# FAN-zero20-SHIM.net
KiCad netlist of a schematic drawn in EAGLE
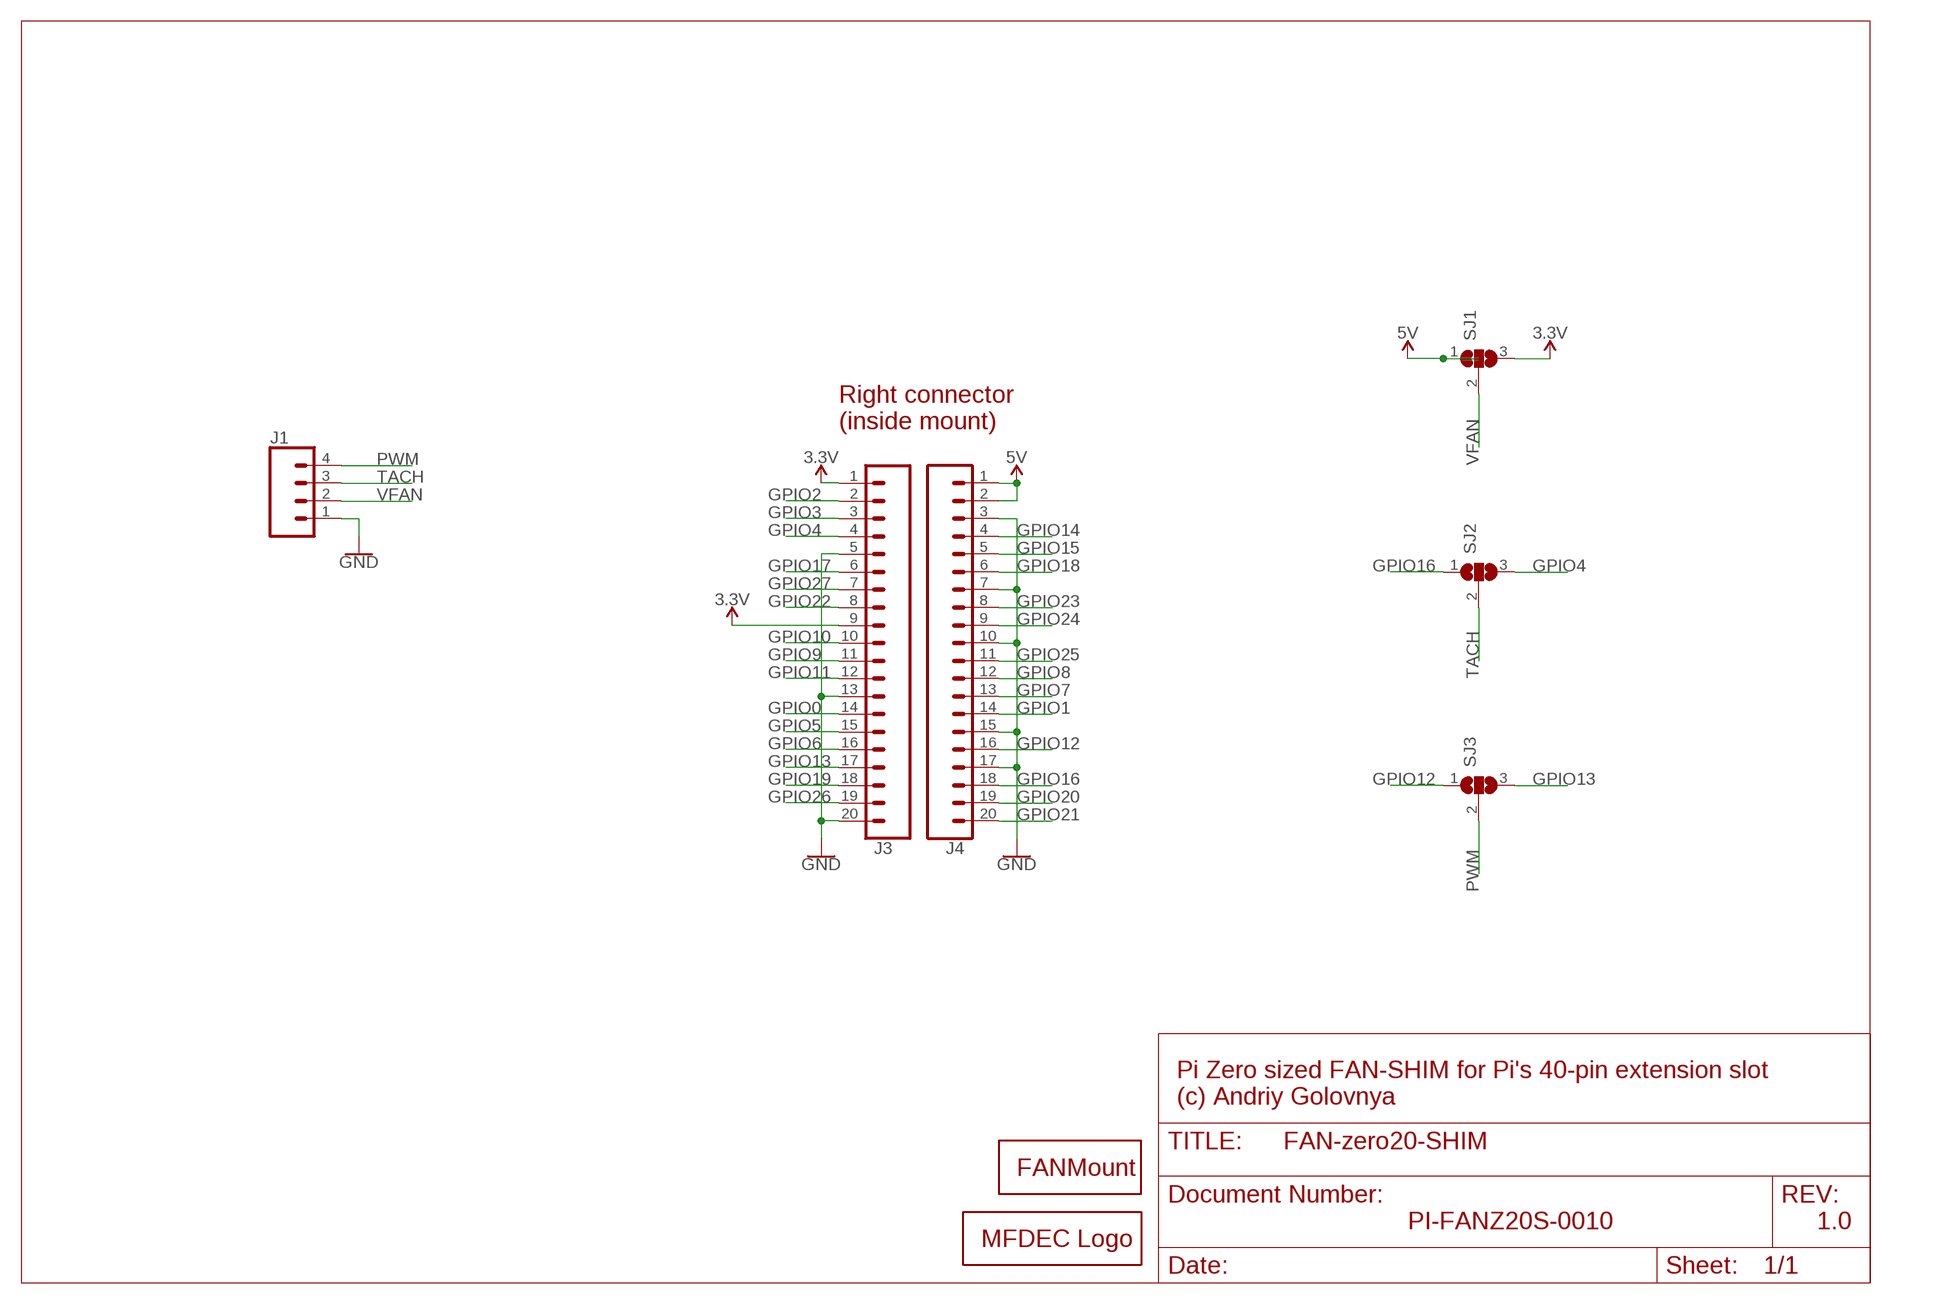
[diagram p0: schematic, sheet 1]

(export (version "E")
  (design (tool "Eeschema 10.0.6"))
  (components
    (comp (ref "FAN1")
      (value "FAN20HO")
      (footprint "eagle-import:FAN20HO")
      (libsource (lib "eagle-import") (part "FAN20HO"))
    )
    (comp (ref "J1")
      (value "CONN_04")
      (footprint "eagle-import:1X04")
      (libsource (lib "eagle-import") (part "CONN_04"))
    )
    (comp (ref "J3")
      (value "CONN_20LOCK")
      (footprint "eagle-import:1X20_LOCK")
      (libsource (lib "eagle-import") (part "CONN_20LOCK"))
    )
    (comp (ref "J4")
      (value "CONN_20LOCK")
      (footprint "eagle-import:1X20_LOCK")
      (libsource (lib "eagle-import") (part "CONN_20LOCK"))
    )
    (comp (ref "LOGO1")
      (value "MFDECLOGO_L_30MM")
      (footprint "eagle-import:MFDEC_L_30MM")
      (libsource (lib "eagle-import") (part "MFDECLOGO_L_30MM"))
    )
    (comp (ref "SJ1")
      (value "SJ2")
      (footprint "eagle-import:SJ_2")
      (libsource (lib "eagle-import") (part "SJ2"))
    )
    (comp (ref "SJ2")
      (value "SJ2")
      (footprint "eagle-import:SJ_2")
      (libsource (lib "eagle-import") (part "SJ2"))
    )
    (comp (ref "SJ3")
      (value "SJ2")
      (footprint "eagle-import:SJ_2")
      (libsource (lib "eagle-import") (part "SJ2"))
    )
  )
  (nets
    (net (code "1") (name "/GPIO0") (class "Default")
      (node (ref "J3") (pin "14") (pinfunction "14_14") (pintype "passive"))
    )
    (net (code "2") (name "/GPIO1") (class "Default")
      (node (ref "J4") (pin "14") (pinfunction "14_14") (pintype "passive"))
    )
    (net (code "3") (name "/GPIO2") (class "Default")
      (node (ref "J3") (pin "2") (pinfunction "2_2") (pintype "passive"))
    )
    (net (code "4") (name "/GPIO3") (class "Default")
      (node (ref "J3") (pin "3") (pinfunction "3_3") (pintype "passive"))
    )
    (net (code "5") (name "/GPIO4") (class "Default")
      (node (ref "J3") (pin "4") (pinfunction "4_4") (pintype "passive"))
      (node (ref "SJ2") (pin "3") (pinfunction "3_3") (pintype "passive"))
    )
    (net (code "6") (name "/GPIO5") (class "Default")
      (node (ref "J3") (pin "15") (pinfunction "15_15") (pintype "passive"))
    )
    (net (code "7") (name "/GPIO6") (class "Default")
      (node (ref "J3") (pin "16") (pinfunction "16_16") (pintype "passive"))
    )
    (net (code "8") (name "/GPIO7") (class "Default")
      (node (ref "J4") (pin "13") (pinfunction "13_13") (pintype "passive"))
    )
    (net (code "9") (name "/GPIO8") (class "Default")
      (node (ref "J4") (pin "12") (pinfunction "12_12") (pintype "passive"))
    )
    (net (code "10") (name "/GPIO9") (class "Default")
      (node (ref "J3") (pin "11") (pinfunction "11_11") (pintype "passive"))
    )
    (net (code "11") (name "/GPIO10") (class "Default")
      (node (ref "J3") (pin "10") (pinfunction "10_10") (pintype "passive"))
    )
    (net (code "12") (name "/GPIO11") (class "Default")
      (node (ref "J3") (pin "12") (pinfunction "12_12") (pintype "passive"))
    )
    (net (code "13") (name "/GPIO12") (class "Default")
      (node (ref "J4") (pin "16") (pinfunction "16_16") (pintype "passive"))
      (node (ref "SJ3") (pin "1") (pinfunction "1_1") (pintype "passive"))
    )
    (net (code "14") (name "/GPIO13") (class "Default")
      (node (ref "J3") (pin "17") (pinfunction "17_17") (pintype "passive"))
      (node (ref "SJ3") (pin "3") (pinfunction "3_3") (pintype "passive"))
    )
    (net (code "15") (name "/GPIO14") (class "Default")
      (node (ref "J4") (pin "4") (pinfunction "4_4") (pintype "passive"))
    )
    (net (code "16") (name "/GPIO15") (class "Default")
      (node (ref "J4") (pin "5") (pinfunction "5_5") (pintype "passive"))
    )
    (net (code "17") (name "/GPIO16") (class "Default")
      (node (ref "J4") (pin "18") (pinfunction "18_18") (pintype "passive"))
      (node (ref "SJ2") (pin "1") (pinfunction "1_1") (pintype "passive"))
    )
    (net (code "18") (name "/GPIO17") (class "Default")
      (node (ref "J3") (pin "6") (pinfunction "6_6") (pintype "passive"))
    )
    (net (code "19") (name "/GPIO18") (class "Default")
      (node (ref "J4") (pin "6") (pinfunction "6_6") (pintype "passive"))
    )
    (net (code "20") (name "/GPIO19") (class "Default")
      (node (ref "J3") (pin "18") (pinfunction "18_18") (pintype "passive"))
    )
    (net (code "21") (name "/GPIO20") (class "Default")
      (node (ref "J4") (pin "19") (pinfunction "19_19") (pintype "passive"))
    )
    (net (code "22") (name "/GPIO21") (class "Default")
      (node (ref "J4") (pin "20") (pinfunction "20_20") (pintype "passive"))
    )
    (net (code "23") (name "/GPIO22") (class "Default")
      (node (ref "J3") (pin "8") (pinfunction "8_8") (pintype "passive"))
    )
    (net (code "24") (name "/GPIO23") (class "Default")
      (node (ref "J4") (pin "8") (pinfunction "8_8") (pintype "passive"))
    )
    (net (code "25") (name "/GPIO24") (class "Default")
      (node (ref "J4") (pin "9") (pinfunction "9_9") (pintype "passive"))
    )
    (net (code "26") (name "/GPIO25") (class "Default")
      (node (ref "J4") (pin "11") (pinfunction "11_11") (pintype "passive"))
    )
    (net (code "27") (name "/GPIO26") (class "Default")
      (node (ref "J3") (pin "19") (pinfunction "19_19") (pintype "passive"))
    )
    (net (code "28") (name "/GPIO27") (class "Default")
      (node (ref "J3") (pin "7") (pinfunction "7_7") (pintype "passive"))
    )
    (net (code "29") (name "/PWM") (class "Default")
      (node (ref "J1") (pin "4") (pinfunction "4_4") (pintype "passive"))
      (node (ref "SJ3") (pin "2") (pinfunction "2_2") (pintype "passive"))
    )
    (net (code "30") (name "/TACH") (class "Default")
      (node (ref "J1") (pin "3") (pinfunction "3_3") (pintype "passive"))
      (node (ref "SJ2") (pin "2") (pinfunction "2_2") (pintype "passive"))
    )
    (net (code "31") (name "/VFAN") (class "Default")
      (node (ref "J1") (pin "2") (pinfunction "2_2") (pintype "passive"))
      (node (ref "SJ1") (pin "2") (pinfunction "2_2") (pintype "passive"))
    )
    (net (code "32") (name "3.3V") (class "Default")
      (node (ref "J3") (pin "1") (pinfunction "1_1") (pintype "passive"))
      (node (ref "J3") (pin "9") (pinfunction "9_9") (pintype "passive"))
      (node (ref "SJ1") (pin "3") (pinfunction "3_3") (pintype "passive"))
    )
    (net (code "33") (name "5V") (class "Default")
      (node (ref "J4") (pin "1") (pinfunction "1_1") (pintype "passive"))
      (node (ref "J4") (pin "2") (pinfunction "2_2") (pintype "passive"))
      (node (ref "SJ1") (pin "1") (pinfunction "1_1") (pintype "passive"))
    )
    (net (code "34") (name "GND") (class "Default")
      (node (ref "J1") (pin "1") (pinfunction "1_1") (pintype "passive"))
      (node (ref "J3") (pin "13") (pinfunction "13_13") (pintype "passive"))
      (node (ref "J3") (pin "20") (pinfunction "20_20") (pintype "passive"))
      (node (ref "J3") (pin "5") (pinfunction "5_5") (pintype "passive"))
      (node (ref "J4") (pin "10") (pinfunction "10_10") (pintype "passive"))
      (node (ref "J4") (pin "15") (pinfunction "15_15") (pintype "passive"))
      (node (ref "J4") (pin "17") (pinfunction "17_17") (pintype "passive"))
      (node (ref "J4") (pin "3") (pinfunction "3_3") (pintype "passive"))
      (node (ref "J4") (pin "7") (pinfunction "7_7") (pintype "passive"))
    )
  )
)
